# shinobi_5v_3V3.net
KiCad netlist of a schematic drawn in EAGLE
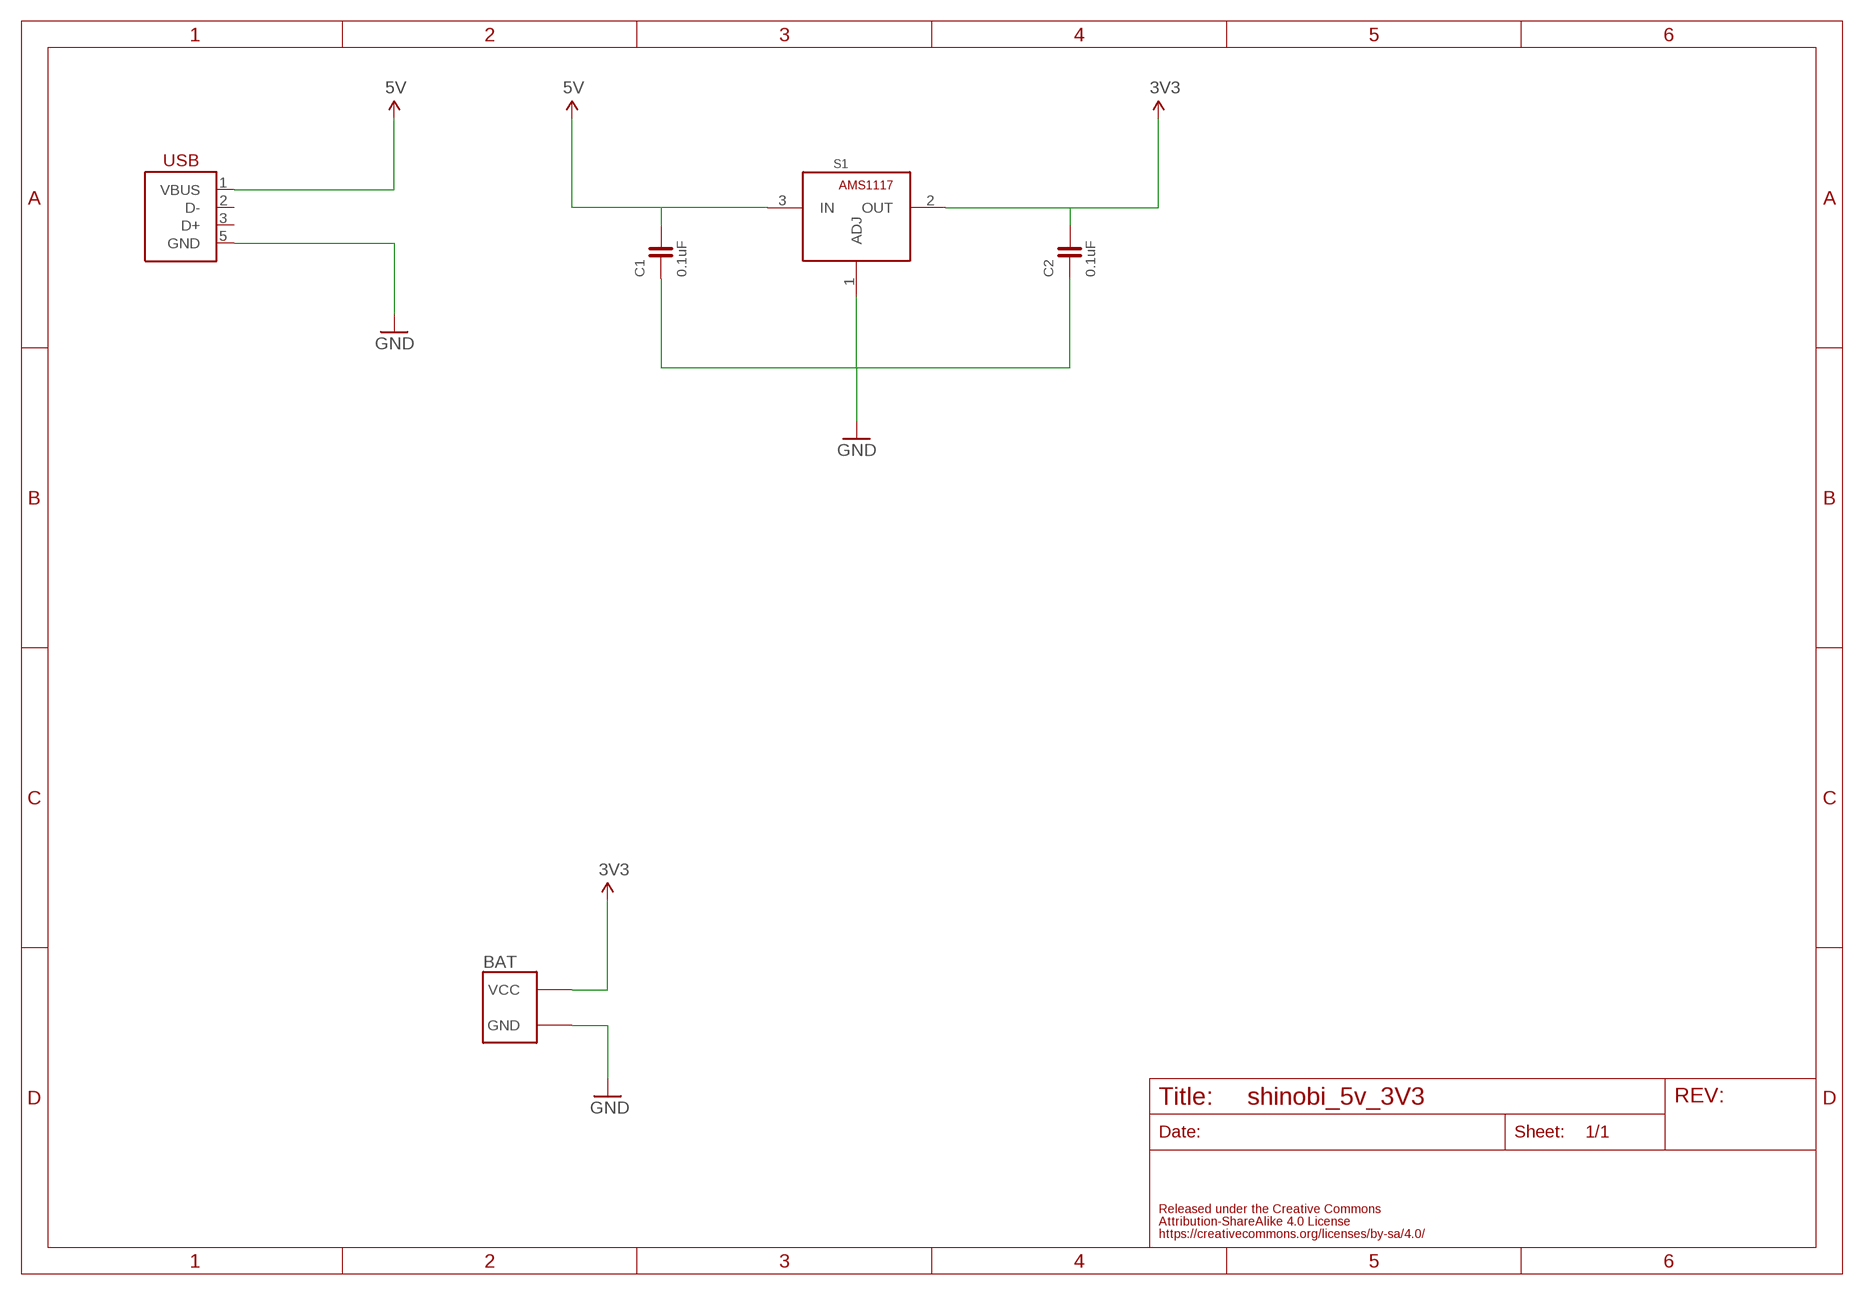
[diagram p0: schematic, sheet 1]

(export (version "E")
  (design (tool "Eeschema 10.0.6"))
  (components
    (comp (ref "BAT")
      (value "FABO_BRICK_2PIN_SIDE")
      (footprint "eagle-import:FABO_BRICK_2PIN_S02B−PASK-2_SILK")
      (libsource (lib "eagle-import") (part "FABO_BRICK_2PIN_SIDE"))
    )
    (comp (ref "C1")
      (value "0.1uF")
      (footprint "eagle-import:0603")
      (libsource (lib "eagle-import") (part "CAPACITOR-0603"))
    )
    (comp (ref "C2")
      (value "0.1uF")
      (footprint "eagle-import:0603")
      (libsource (lib "eagle-import") (part "CAPACITOR-0603"))
    )
    (comp (ref "S1")
      (value "AMS1117")
      (footprint "eagle-import:SOT-223-3")
      (libsource (lib "eagle-import") (part "AMS1117"))
    )
    (comp (ref "USB1")
      (value "USB-MICRO_B_SMT_HIROSE")
      (footprint "eagle-import:ZX62R-B-5P")
      (libsource (lib "eagle-import") (part "USB-MICRO_B_SMT_HIROSE"))
    )
  )
  (nets
    (net (code "1") (name "3V3") (class "Default")
      (node (ref "BAT") (pin "VCC") (pinfunction "VCC_VCC") (pintype "bidirectional"))
      (node (ref "C2") (pin "2") (pinfunction "2_2") (pintype "passive"))
      (node (ref "S1") (pin "2") (pinfunction "OUT_2") (pintype "bidirectional"))
    )
    (net (code "2") (name "5V") (class "Default")
      (node (ref "C1") (pin "2") (pinfunction "2_2") (pintype "passive"))
      (node (ref "S1") (pin "3") (pinfunction "IN_3") (pintype "bidirectional"))
      (node (ref "USB1") (pin "1") (pinfunction "VBUS_1") (pintype "bidirectional"))
    )
    (net (code "3") (name "GND") (class "Default")
      (node (ref "BAT") (pin "GND") (pinfunction "GND_GND") (pintype "bidirectional"))
      (node (ref "C1") (pin "1") (pinfunction "1_1") (pintype "passive"))
      (node (ref "C2") (pin "1") (pinfunction "1_1") (pintype "passive"))
      (node (ref "S1") (pin "1") (pinfunction "ADJ_1") (pintype "bidirectional"))
      (node (ref "USB1") (pin "5") (pinfunction "GND_5") (pintype "bidirectional"))
    )
    (net (code "4") (name "unconnected-(USB1-D+-Pad3)") (class "Default")
      (node (ref "USB1") (pin "3") (pinfunction "D+_3") (pintype "bidirectional"))
    )
    (net (code "5") (name "unconnected-(USB1-D--Pad2)") (class "Default")
      (node (ref "USB1") (pin "2") (pinfunction "D-_2") (pintype "bidirectional"))
    )
  )
)
